# Finger_LED_Board.net
KiCad netlist of a schematic drawn in EAGLE
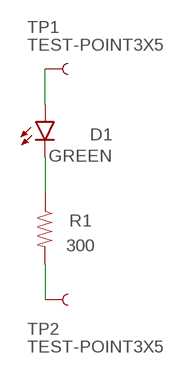
[diagram p0: schematic, sheet 1]

(export (version "E")
  (design (tool "Eeschema 10.0.6"))
  (components
    (comp (ref "D1")
      (value "GREEN")
      (footprint "eagle-import:LED-1206")
      (libsource (lib "eagle-import") (part "LED-GREEN1206"))
    )
    (comp (ref "R1")
      (value "300")
      (footprint "eagle-import:0603")
      (libsource (lib "eagle-import") (part "300OHM-0603-1/10W-1%"))
    )
    (comp (ref "TP1")
      (value "TEST-POINT3X5")
      (footprint "eagle-import:PAD.03X.05")
      (libsource (lib "eagle-import") (part "TEST-POINT3X5"))
    )
    (comp (ref "TP2")
      (value "TEST-POINT3X5")
      (footprint "eagle-import:PAD.03X.05")
      (libsource (lib "eagle-import") (part "TEST-POINT3X5"))
    )
  )
  (nets
    (net (code "1") (name "Net-(D1-PadC)") (class "Default")
      (node (ref "D1") (pin "C") (pinfunction "C_C") (pintype "passive"))
      (node (ref "R1") (pin "1") (pinfunction "1_1") (pintype "passive"))
    )
    (net (code "2") (name "Net-(TP1-1)") (class "Default")
      (node (ref "D1") (pin "A") (pinfunction "A_A") (pintype "passive"))
      (node (ref "TP1") (pin "P$1") (pinfunction "1_P$1") (pintype "bidirectional"))
    )
    (net (code "3") (name "Net-(TP2-1)") (class "Default")
      (node (ref "R1") (pin "2") (pinfunction "2_2") (pintype "passive"))
      (node (ref "TP2") (pin "P$1") (pinfunction "1_P$1") (pintype "bidirectional"))
    )
  )
)
